# tmp117.net
KiCad netlist of a schematic drawn in EAGLE
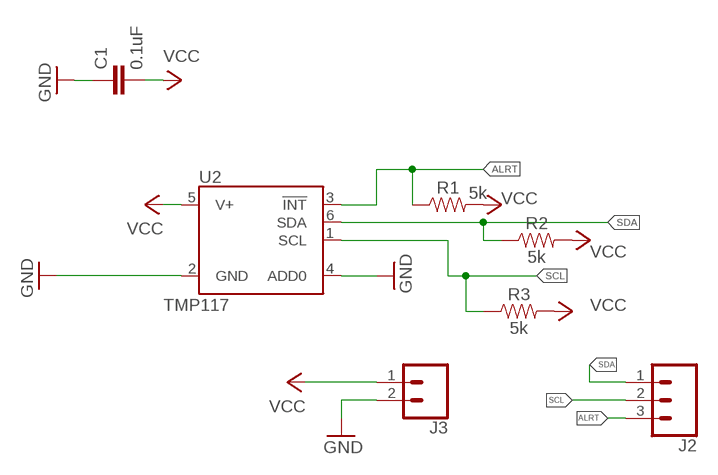
[diagram p0: schematic, sheet 1]

(export (version "E")
  (design (tool "Eeschema 10.0.6"))
  (components
    (comp (ref "C1")
      (value "0.1uF")
      (footprint "eagle-import:0603")
      (libsource (lib "eagle-import") (part "2.2UF-0603-10V-20%"))
    )
    (comp (ref "J2")
      (value "CONN_03")
      (footprint "eagle-import:1X03")
      (libsource (lib "eagle-import") (part "CONN_03"))
    )
    (comp (ref "J3")
      (value "CONN_02")
      (footprint "eagle-import:1X02")
      (libsource (lib "eagle-import") (part "CONN_02"))
    )
    (comp (ref "R1")
      (value "5k")
      (footprint "eagle-import:0603")
      (libsource (lib "eagle-import") (part "1.6KOHM-0603-1/10W-1%"))
    )
    (comp (ref "R2")
      (value "5k")
      (footprint "eagle-import:0603")
      (libsource (lib "eagle-import") (part "1.6KOHM-0603-1/10W-1%"))
    )
    (comp (ref "R3")
      (value "5k")
      (footprint "eagle-import:0603")
      (libsource (lib "eagle-import") (part "1.6KOHM-0603-1/10W-1%"))
    )
    (comp (ref "U2")
      (value "TMP117")
      (footprint "eagle-import:TMP117")
      (libsource (lib "eagle-import") (part "TMP117"))
    )
  )
  (nets
    (net (code "1") (name "ALRT") (class "Default")
      (node (ref "J2") (pin "3") (pinfunction "3_3") (pintype "passive"))
      (node (ref "R1") (pin "1") (pinfunction "1_1") (pintype "passive"))
      (node (ref "U2") (pin "3") (pinfunction "~{INT}_3") (pintype "bidirectional"))
    )
    (net (code "2") (name "GND") (class "Default")
      (node (ref "C1") (pin "1") (pinfunction "1_1") (pintype "passive"))
      (node (ref "J3") (pin "2") (pinfunction "2_2") (pintype "passive"))
      (node (ref "U2") (pin "2") (pinfunction "GND_2") (pintype "bidirectional"))
      (node (ref "U2") (pin "4") (pinfunction "ADD0_4") (pintype "bidirectional"))
    )
    (net (code "3") (name "SCL") (class "Default")
      (node (ref "J2") (pin "2") (pinfunction "2_2") (pintype "passive"))
      (node (ref "R3") (pin "1") (pinfunction "1_1") (pintype "passive"))
      (node (ref "U2") (pin "1") (pinfunction "SCL_1") (pintype "bidirectional"))
    )
    (net (code "4") (name "SDA") (class "Default")
      (node (ref "J2") (pin "1") (pinfunction "1_1") (pintype "passive"))
      (node (ref "R2") (pin "1") (pinfunction "1_1") (pintype "passive"))
      (node (ref "U2") (pin "6") (pinfunction "SDA_6") (pintype "bidirectional"))
    )
    (net (code "5") (name "VCC") (class "Default")
      (node (ref "C1") (pin "2") (pinfunction "2_2") (pintype "passive"))
      (node (ref "J3") (pin "1") (pinfunction "1_1") (pintype "passive"))
      (node (ref "R1") (pin "2") (pinfunction "2_2") (pintype "passive"))
      (node (ref "R2") (pin "2") (pinfunction "2_2") (pintype "passive"))
      (node (ref "R3") (pin "2") (pinfunction "2_2") (pintype "passive"))
      (node (ref "U2") (pin "5") (pinfunction "V+_5") (pintype "power_in"))
    )
  )
)
